# eurofima.net
KiCad netlist of a schematic drawn in EAGLE
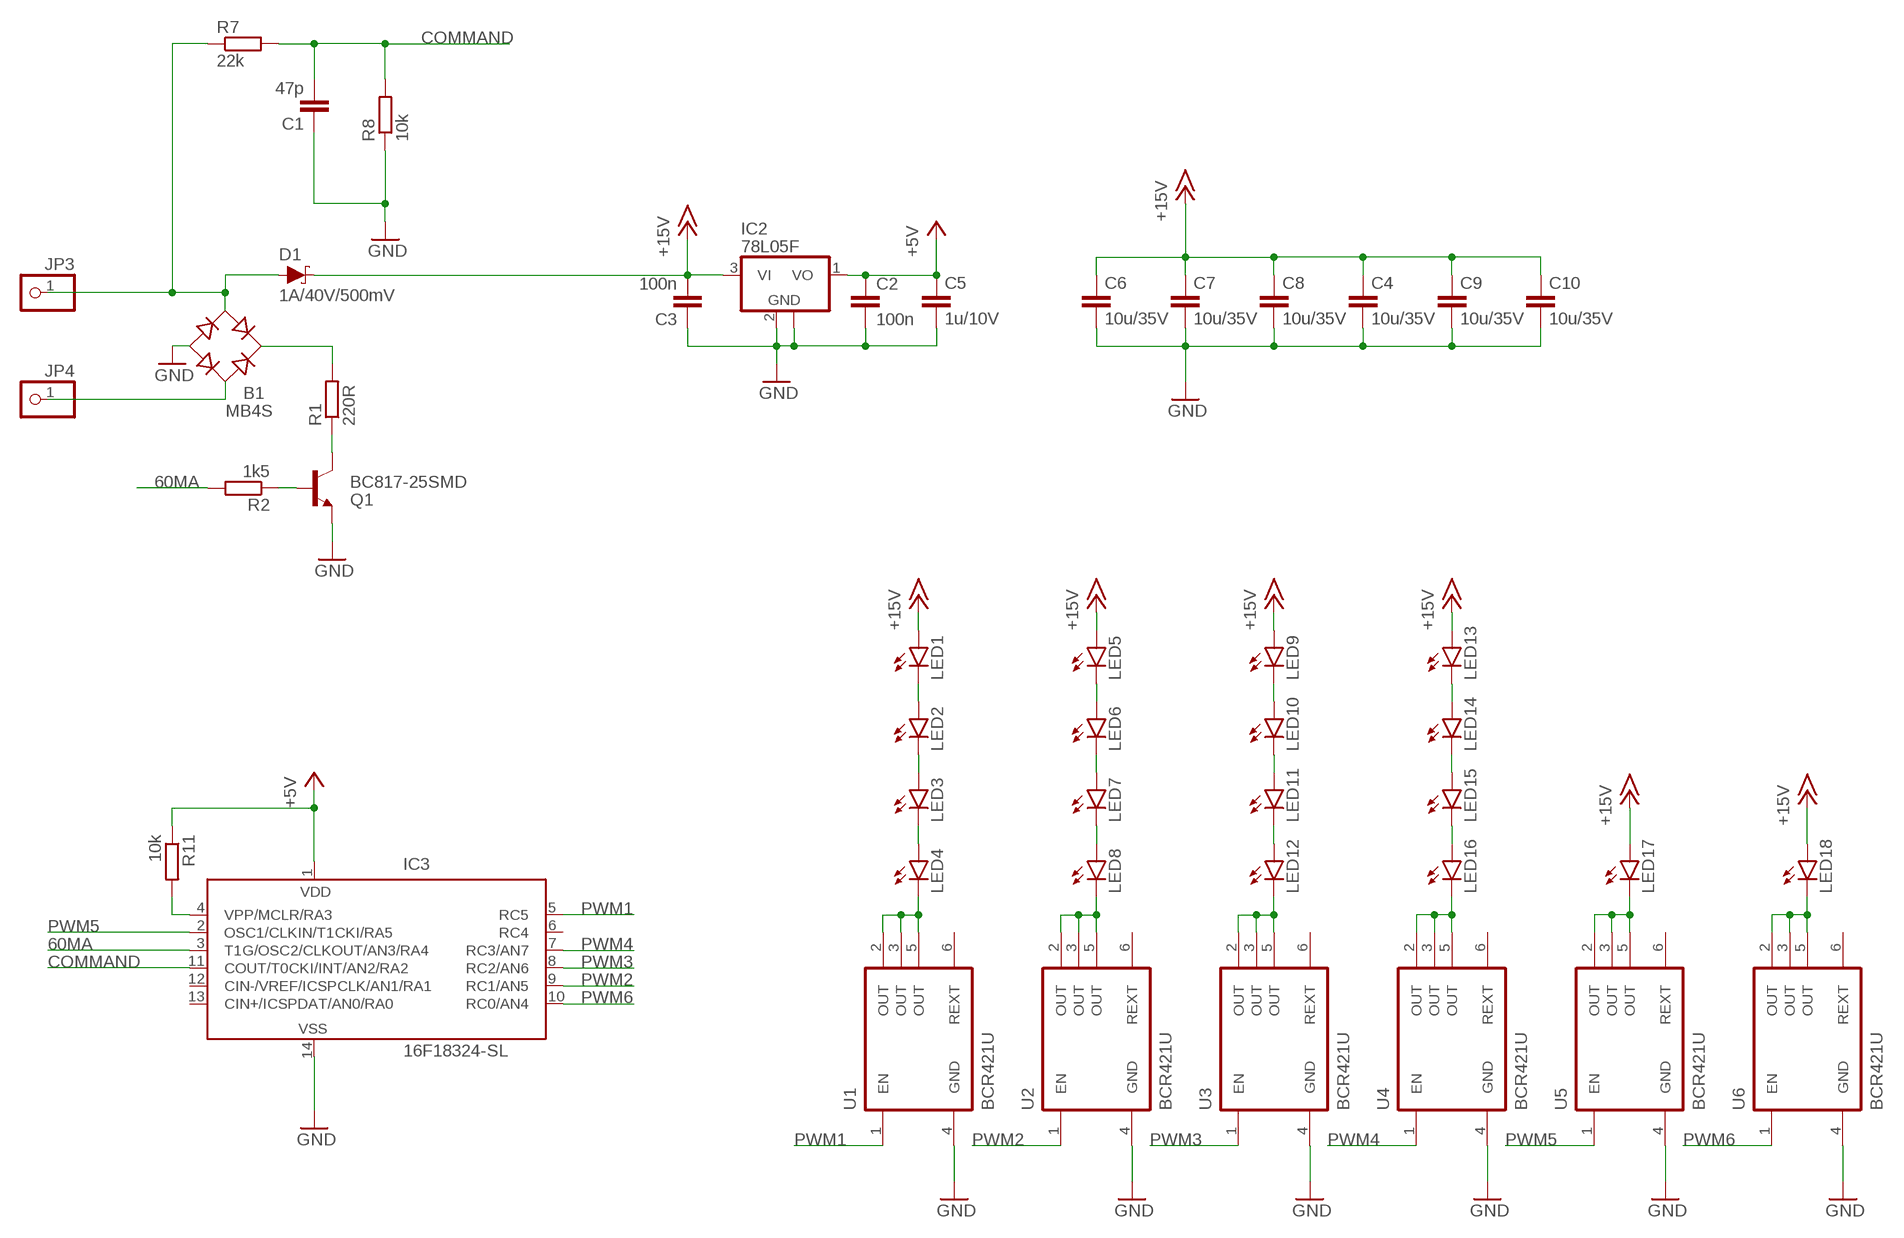
[diagram p0: schematic, sheet 1]

(export (version "E")
  (design (tool "Eeschema 10.0.6"))
  (components
    (comp (ref "B1")
      (value "MB4S")
      (footprint "eagle-import:SOIC-4")
      (libsource (lib "eagle-import") (part "MBS4"))
    )
    (comp (ref "C1")
      (value "47p")
      (footprint "eagle-import:C0805")
      (libsource (lib "eagle-import") (part "C-EUC0805"))
    )
    (comp (ref "C2")
      (value "100n")
      (footprint "eagle-import:C3216")
      (libsource (lib "eagle-import") (part "C-EUC3216"))
    )
    (comp (ref "C3")
      (value "100n")
      (footprint "eagle-import:C3216")
      (libsource (lib "eagle-import") (part "C-EUC3216"))
    )
    (comp (ref "C4")
      (value "10u/35V")
      (footprint "eagle-import:C3216")
      (libsource (lib "eagle-import") (part "C-EUC3216"))
    )
    (comp (ref "C5")
      (value "1u/10V")
      (footprint "eagle-import:C3216")
      (libsource (lib "eagle-import") (part "C-EUC3216"))
    )
    (comp (ref "C6")
      (value "10u/35V")
      (footprint "eagle-import:C3216")
      (libsource (lib "eagle-import") (part "C-EUC3216"))
    )
    (comp (ref "C7")
      (value "10u/35V")
      (footprint "eagle-import:C3216")
      (libsource (lib "eagle-import") (part "C-EUC3216"))
    )
    (comp (ref "C8")
      (value "10u/35V")
      (footprint "eagle-import:C3216")
      (libsource (lib "eagle-import") (part "C-EUC3216"))
    )
    (comp (ref "C9")
      (value "10u/35V")
      (footprint "eagle-import:C3216")
      (libsource (lib "eagle-import") (part "C-EUC3216"))
    )
    (comp (ref "C10")
      (value "10u/35V")
      (footprint "eagle-import:C3216")
      (libsource (lib "eagle-import") (part "C-EUC3216"))
    )
    (comp (ref "D1")
      (value "1A/40V/500mV")
      (footprint "eagle-import:SMA-DIODE")
      (libsource (lib "eagle-import") (part "DIODE-SCHOTTKY-SS14"))
    )
    (comp (ref "IC2")
      (value "78L05F")
      (footprint "eagle-import:SOT89")
      (libsource (lib "eagle-import") (part "78LF05"))
    )
    (comp (ref "IC3")
      (value "16F18324-SL")
      (footprint "eagle-import:SO-14")
      (fields (field (name "MF") "MICROCHIP") (field (name "MPN") "PIC16F676-I/SL"))
      (libsource (lib "eagle-import") (part "PIC16F676SL"))
    )
    (comp (ref "JP3")
      (value "PINHD-1X1")
      (footprint "eagle-import:1X01")
      (libsource (lib "eagle-import") (part "PINHD-1X1"))
    )
    (comp (ref "JP4")
      (value "PINHD-1X1")
      (footprint "eagle-import:1X01")
      (libsource (lib "eagle-import") (part "PINHD-1X1"))
    )
    (comp (ref "LED1")
      (value "LEDKA-3528ASYC")
      (footprint "eagle-import:KA-3528ASYC")
      (libsource (lib "eagle-import") (part "LEDKA-3528ASYC"))
    )
    (comp (ref "LED2")
      (value "LEDKA-3528ASYC")
      (footprint "eagle-import:KA-3528ASYC")
      (libsource (lib "eagle-import") (part "LEDKA-3528ASYC"))
    )
    (comp (ref "LED3")
      (value "LEDKA-3528ASYC")
      (footprint "eagle-import:KA-3528ASYC")
      (libsource (lib "eagle-import") (part "LEDKA-3528ASYC"))
    )
    (comp (ref "LED4")
      (value "LEDKA-3528ASYC")
      (footprint "eagle-import:KA-3528ASYC")
      (libsource (lib "eagle-import") (part "LEDKA-3528ASYC"))
    )
    (comp (ref "LED5")
      (value "LEDKA-3528ASYC")
      (footprint "eagle-import:KA-3528ASYC")
      (libsource (lib "eagle-import") (part "LEDKA-3528ASYC"))
    )
    (comp (ref "LED6")
      (value "LEDKA-3528ASYC")
      (footprint "eagle-import:KA-3528ASYC")
      (libsource (lib "eagle-import") (part "LEDKA-3528ASYC"))
    )
    (comp (ref "LED7")
      (value "LEDKA-3528ASYC")
      (footprint "eagle-import:KA-3528ASYC")
      (libsource (lib "eagle-import") (part "LEDKA-3528ASYC"))
    )
    (comp (ref "LED8")
      (value "LEDKA-3528ASYC")
      (footprint "eagle-import:KA-3528ASYC")
      (libsource (lib "eagle-import") (part "LEDKA-3528ASYC"))
    )
    (comp (ref "LED9")
      (value "LEDKA-3528ASYC")
      (footprint "eagle-import:KA-3528ASYC")
      (libsource (lib "eagle-import") (part "LEDKA-3528ASYC"))
    )
    (comp (ref "LED10")
      (value "LEDKA-3528ASYC")
      (footprint "eagle-import:KA-3528ASYC")
      (libsource (lib "eagle-import") (part "LEDKA-3528ASYC"))
    )
    (comp (ref "LED11")
      (value "LEDKA-3528ASYC")
      (footprint "eagle-import:KA-3528ASYC")
      (libsource (lib "eagle-import") (part "LEDKA-3528ASYC"))
    )
    (comp (ref "LED12")
      (value "LEDKA-3528ASYC")
      (footprint "eagle-import:KA-3528ASYC")
      (libsource (lib "eagle-import") (part "LEDKA-3528ASYC"))
    )
    (comp (ref "LED13")
      (value "LEDKA-3528ASYC")
      (footprint "eagle-import:KA-3528ASYC")
      (libsource (lib "eagle-import") (part "LEDKA-3528ASYC"))
    )
    (comp (ref "LED14")
      (value "LEDKA-3528ASYC")
      (footprint "eagle-import:KA-3528ASYC")
      (libsource (lib "eagle-import") (part "LEDKA-3528ASYC"))
    )
    (comp (ref "LED15")
      (value "LEDKA-3528ASYC")
      (footprint "eagle-import:KA-3528ASYC")
      (libsource (lib "eagle-import") (part "LEDKA-3528ASYC"))
    )
    (comp (ref "LED16")
      (value "LEDKA-3528ASYC")
      (footprint "eagle-import:KA-3528ASYC")
      (libsource (lib "eagle-import") (part "LEDKA-3528ASYC"))
    )
    (comp (ref "LED17")
      (value "LED3MM")
      (footprint "eagle-import:LED3MM")
      (libsource (lib "eagle-import") (part "LED3MM"))
    )
    (comp (ref "LED18")
      (value "LED3MM")
      (footprint "eagle-import:LED3MM")
      (libsource (lib "eagle-import") (part "LED3MM"))
    )
    (comp (ref "Q1")
      (value "BC817-25SMD")
      (footprint "eagle-import:SOT23-BEC")
      (libsource (lib "eagle-import") (part "BC817SMD-25"))
    )
    (comp (ref "R1")
      (value "220R")
      (footprint "eagle-import:R1206")
      (libsource (lib "eagle-import") (part "R-EU_R1206"))
    )
    (comp (ref "R2")
      (value "1k5")
      (footprint "eagle-import:R1206")
      (libsource (lib "eagle-import") (part "R-EU_R1206"))
    )
    (comp (ref "R7")
      (value "22k")
      (footprint "eagle-import:R1206")
      (libsource (lib "eagle-import") (part "R-EU_R1206"))
    )
    (comp (ref "R8")
      (value "10k")
      (footprint "eagle-import:R1206")
      (libsource (lib "eagle-import") (part "R-EU_R1206"))
    )
    (comp (ref "R11")
      (value "10k")
      (footprint "eagle-import:R1206")
      (libsource (lib "eagle-import") (part "R-EU_R1206"))
    )
    (comp (ref "U1")
      (value "BCR421U")
      (footprint "eagle-import:SC74-6")
      (fields (field (name "MF") "Infineon"))
      (libsource (lib "eagle-import") (part "BCR421U"))
    )
    (comp (ref "U2")
      (value "BCR421U")
      (footprint "eagle-import:SC74-6")
      (fields (field (name "MF") "Infineon"))
      (libsource (lib "eagle-import") (part "BCR421U"))
    )
    (comp (ref "U3")
      (value "BCR421U")
      (footprint "eagle-import:SC74-6")
      (fields (field (name "MF") "Infineon"))
      (libsource (lib "eagle-import") (part "BCR421U"))
    )
    (comp (ref "U4")
      (value "BCR421U")
      (footprint "eagle-import:SC74-6")
      (fields (field (name "MF") "Infineon"))
      (libsource (lib "eagle-import") (part "BCR421U"))
    )
    (comp (ref "U5")
      (value "BCR421U")
      (footprint "eagle-import:SC74-6")
      (fields (field (name "MF") "Infineon"))
      (libsource (lib "eagle-import") (part "BCR421U"))
    )
    (comp (ref "U6")
      (value "BCR421U")
      (footprint "eagle-import:SC74-6")
      (fields (field (name "MF") "Infineon"))
      (libsource (lib "eagle-import") (part "BCR421U"))
    )
  )
  (nets
    (net (code "1") (name "+5V") (class "Default")
      (node (ref "C2") (pin "1") (pinfunction "1_1") (pintype "passive"))
      (node (ref "C5") (pin "1") (pinfunction "1_1") (pintype "passive"))
      (node (ref "IC2") (pin "1") (pinfunction "VO_1") (pintype "passive"))
      (node (ref "IC3") (pin "1") (pinfunction "VDD_1") (pintype "power_in"))
      (node (ref "R11") (pin "1") (pinfunction "1_1") (pintype "passive"))
    )
    (net (code "2") (name "+15V") (class "Default")
      (node (ref "C10") (pin "1") (pinfunction "1_1") (pintype "passive"))
      (node (ref "C3") (pin "2") (pinfunction "2_2") (pintype "passive"))
      (node (ref "C4") (pin "1") (pinfunction "1_1") (pintype "passive"))
      (node (ref "C6") (pin "1") (pinfunction "1_1") (pintype "passive"))
      (node (ref "C7") (pin "1") (pinfunction "1_1") (pintype "passive"))
      (node (ref "C8") (pin "1") (pinfunction "1_1") (pintype "passive"))
      (node (ref "C9") (pin "1") (pinfunction "1_1") (pintype "passive"))
      (node (ref "D1") (pin "C") (pinfunction "C_C") (pintype "passive"))
      (node (ref "IC2") (pin "3") (pinfunction "VI_3") (pintype "input"))
      (node (ref "LED1") (pin "A") (pinfunction "A_A") (pintype "passive"))
      (node (ref "LED13") (pin "A") (pinfunction "A_A") (pintype "passive"))
      (node (ref "LED17") (pin "A") (pinfunction "A_A") (pintype "passive"))
      (node (ref "LED18") (pin "A") (pinfunction "A_A") (pintype "passive"))
      (node (ref "LED5") (pin "A") (pinfunction "A_A") (pintype "passive"))
      (node (ref "LED9") (pin "A") (pinfunction "A_A") (pintype "passive"))
    )
    (net (code "3") (name "/60MA") (class "Default")
      (node (ref "IC3") (pin "3") (pinfunction "T1G/OSC2/CLKOUT/AN3/RA4_3") (pintype "bidirectional"))
      (node (ref "R2") (pin "2") (pinfunction "2_2") (pintype "passive"))
    )
    (net (code "4") (name "/COMMAND") (class "Default")
      (node (ref "C1") (pin "2") (pinfunction "2_2") (pintype "passive"))
      (node (ref "IC3") (pin "11") (pinfunction "COUT/T0CKI/INT/AN2/RA2_11") (pintype "bidirectional"))
      (node (ref "R7") (pin "2") (pinfunction "2_2") (pintype "passive"))
      (node (ref "R8") (pin "2") (pinfunction "2_2") (pintype "passive"))
    )
    (net (code "5") (name "/PWM1") (class "Default")
      (node (ref "IC3") (pin "5") (pinfunction "RC5_5") (pintype "bidirectional"))
      (node (ref "U1") (pin "1") (pinfunction "EN_1") (pintype "input"))
    )
    (net (code "6") (name "/PWM2") (class "Default")
      (node (ref "IC3") (pin "9") (pinfunction "RC1/AN5_9") (pintype "bidirectional"))
      (node (ref "U2") (pin "1") (pinfunction "EN_1") (pintype "input"))
    )
    (net (code "7") (name "/PWM3") (class "Default")
      (node (ref "IC3") (pin "8") (pinfunction "RC2/AN6_8") (pintype "bidirectional"))
      (node (ref "U3") (pin "1") (pinfunction "EN_1") (pintype "input"))
    )
    (net (code "8") (name "/PWM4") (class "Default")
      (node (ref "IC3") (pin "7") (pinfunction "RC3/AN7_7") (pintype "bidirectional"))
      (node (ref "U4") (pin "1") (pinfunction "EN_1") (pintype "input"))
    )
    (net (code "9") (name "/PWM5") (class "Default")
      (node (ref "IC3") (pin "2") (pinfunction "OSC1/CLKIN/T1CKI/RA5_2") (pintype "bidirectional"))
      (node (ref "U5") (pin "1") (pinfunction "EN_1") (pintype "input"))
    )
    (net (code "10") (name "/PWM6") (class "Default")
      (node (ref "IC3") (pin "10") (pinfunction "RC0/AN4_10") (pintype "bidirectional"))
      (node (ref "U6") (pin "1") (pinfunction "EN_1") (pintype "input"))
    )
    (net (code "11") (name "GND") (class "Default")
      (node (ref "B1") (pin "-") (pinfunction "-_-") (pintype "passive"))
      (node (ref "C1") (pin "1") (pinfunction "1_1") (pintype "passive"))
      (node (ref "C10") (pin "2") (pinfunction "2_2") (pintype "passive"))
      (node (ref "C2") (pin "2") (pinfunction "2_2") (pintype "passive"))
      (node (ref "C3") (pin "1") (pinfunction "1_1") (pintype "passive"))
      (node (ref "C4") (pin "2") (pinfunction "2_2") (pintype "passive"))
      (node (ref "C5") (pin "2") (pinfunction "2_2") (pintype "passive"))
      (node (ref "C6") (pin "2") (pinfunction "2_2") (pintype "passive"))
      (node (ref "C7") (pin "2") (pinfunction "2_2") (pintype "passive"))
      (node (ref "C8") (pin "2") (pinfunction "2_2") (pintype "passive"))
      (node (ref "C9") (pin "2") (pinfunction "2_2") (pintype "passive"))
      (node (ref "IC2") (pin "2") (pinfunction "GND_2") (pintype "passive"))
      (node (ref "IC2") (pin "2@1") (pinfunction "GND_2@1") (pintype "passive"))
      (node (ref "IC3") (pin "14") (pinfunction "VSS_14") (pintype "power_in"))
      (node (ref "Q1") (pin "E") (pinfunction "E_E") (pintype "passive"))
      (node (ref "R8") (pin "1") (pinfunction "1_1") (pintype "passive"))
      (node (ref "U1") (pin "4") (pinfunction "GND_4") (pintype "input"))
      (node (ref "U2") (pin "4") (pinfunction "GND_4") (pintype "input"))
      (node (ref "U3") (pin "4") (pinfunction "GND_4") (pintype "input"))
      (node (ref "U4") (pin "4") (pinfunction "GND_4") (pintype "input"))
      (node (ref "U5") (pin "4") (pinfunction "GND_4") (pintype "input"))
      (node (ref "U6") (pin "4") (pinfunction "GND_4") (pintype "input"))
    )
    (net (code "12") (name "Net-(B1-AC1)") (class "Default")
      (node (ref "B1") (pin "~1") (pinfunction "AC1_~1") (pintype "passive"))
      (node (ref "D1") (pin "A") (pinfunction "A_A") (pintype "passive"))
      (node (ref "JP3") (pin "1") (pinfunction "1_1") (pintype "passive"))
      (node (ref "R7") (pin "1") (pinfunction "1_1") (pintype "passive"))
    )
    (net (code "13") (name "Net-(B1-AC2)") (class "Default")
      (node (ref "B1") (pin "~2") (pinfunction "AC2_~2") (pintype "passive"))
      (node (ref "JP4") (pin "1") (pinfunction "1_1") (pintype "passive"))
    )
    (net (code "14") (name "Net-(B1-Pad+)") (class "Default")
      (node (ref "B1") (pin "+") (pinfunction "+_+") (pintype "passive"))
      (node (ref "R1") (pin "2") (pinfunction "2_2") (pintype "passive"))
    )
    (net (code "15") (name "Net-(IC3-VPP{slash}MCLR{slash}RA3)") (class "Default")
      (node (ref "IC3") (pin "4") (pinfunction "VPP/MCLR/RA3_4") (pintype "input"))
      (node (ref "R11") (pin "2") (pinfunction "2_2") (pintype "passive"))
    )
    (net (code "16") (name "Net-(LED1-PadC)") (class "Default")
      (node (ref "LED1") (pin "C") (pinfunction "C_C") (pintype "passive"))
      (node (ref "LED2") (pin "A") (pinfunction "A_A") (pintype "passive"))
    )
    (net (code "17") (name "Net-(LED2-PadC)") (class "Default")
      (node (ref "LED2") (pin "C") (pinfunction "C_C") (pintype "passive"))
      (node (ref "LED3") (pin "A") (pinfunction "A_A") (pintype "passive"))
    )
    (net (code "18") (name "Net-(LED3-PadC)") (class "Default")
      (node (ref "LED3") (pin "C") (pinfunction "C_C") (pintype "passive"))
      (node (ref "LED4") (pin "A") (pinfunction "A_A") (pintype "passive"))
    )
    (net (code "19") (name "Net-(LED4-PadC)") (class "Default")
      (node (ref "LED4") (pin "C") (pinfunction "C_C") (pintype "passive"))
      (node (ref "U1") (pin "2") (pinfunction "OUT_2") (pintype "open_collector"))
      (node (ref "U1") (pin "3") (pinfunction "OUT_3") (pintype "open_collector"))
      (node (ref "U1") (pin "5") (pinfunction "OUT_5") (pintype "open_collector"))
    )
    (net (code "20") (name "Net-(LED5-PadC)") (class "Default")
      (node (ref "LED5") (pin "C") (pinfunction "C_C") (pintype "passive"))
      (node (ref "LED6") (pin "A") (pinfunction "A_A") (pintype "passive"))
    )
    (net (code "21") (name "Net-(LED6-PadC)") (class "Default")
      (node (ref "LED6") (pin "C") (pinfunction "C_C") (pintype "passive"))
      (node (ref "LED7") (pin "A") (pinfunction "A_A") (pintype "passive"))
    )
    (net (code "22") (name "Net-(LED7-PadC)") (class "Default")
      (node (ref "LED7") (pin "C") (pinfunction "C_C") (pintype "passive"))
      (node (ref "LED8") (pin "A") (pinfunction "A_A") (pintype "passive"))
    )
    (net (code "23") (name "Net-(LED8-PadC)") (class "Default")
      (node (ref "LED8") (pin "C") (pinfunction "C_C") (pintype "passive"))
      (node (ref "U2") (pin "2") (pinfunction "OUT_2") (pintype "open_collector"))
      (node (ref "U2") (pin "3") (pinfunction "OUT_3") (pintype "open_collector"))
      (node (ref "U2") (pin "5") (pinfunction "OUT_5") (pintype "open_collector"))
    )
    (net (code "24") (name "Net-(LED10-PadA)") (class "Default")
      (node (ref "LED10") (pin "A") (pinfunction "A_A") (pintype "passive"))
      (node (ref "LED9") (pin "C") (pinfunction "C_C") (pintype "passive"))
    )
    (net (code "25") (name "Net-(LED10-PadC)") (class "Default")
      (node (ref "LED10") (pin "C") (pinfunction "C_C") (pintype "passive"))
      (node (ref "LED11") (pin "A") (pinfunction "A_A") (pintype "passive"))
    )
    (net (code "26") (name "Net-(LED11-PadC)") (class "Default")
      (node (ref "LED11") (pin "C") (pinfunction "C_C") (pintype "passive"))
      (node (ref "LED12") (pin "A") (pinfunction "A_A") (pintype "passive"))
    )
    (net (code "27") (name "Net-(LED12-PadC)") (class "Default")
      (node (ref "LED12") (pin "C") (pinfunction "C_C") (pintype "passive"))
      (node (ref "U3") (pin "2") (pinfunction "OUT_2") (pintype "open_collector"))
      (node (ref "U3") (pin "3") (pinfunction "OUT_3") (pintype "open_collector"))
      (node (ref "U3") (pin "5") (pinfunction "OUT_5") (pintype "open_collector"))
    )
    (net (code "28") (name "Net-(LED13-PadC)") (class "Default")
      (node (ref "LED13") (pin "C") (pinfunction "C_C") (pintype "passive"))
      (node (ref "LED14") (pin "A") (pinfunction "A_A") (pintype "passive"))
    )
    (net (code "29") (name "Net-(LED14-PadC)") (class "Default")
      (node (ref "LED14") (pin "C") (pinfunction "C_C") (pintype "passive"))
      (node (ref "LED15") (pin "A") (pinfunction "A_A") (pintype "passive"))
    )
    (net (code "30") (name "Net-(LED15-PadC)") (class "Default")
      (node (ref "LED15") (pin "C") (pinfunction "C_C") (pintype "passive"))
      (node (ref "LED16") (pin "A") (pinfunction "A_A") (pintype "passive"))
    )
    (net (code "31") (name "Net-(LED16-PadC)") (class "Default")
      (node (ref "LED16") (pin "C") (pinfunction "C_C") (pintype "passive"))
      (node (ref "U4") (pin "2") (pinfunction "OUT_2") (pintype "open_collector"))
      (node (ref "U4") (pin "3") (pinfunction "OUT_3") (pintype "open_collector"))
      (node (ref "U4") (pin "5") (pinfunction "OUT_5") (pintype "open_collector"))
    )
    (net (code "32") (name "Net-(LED17-C)") (class "Default")
      (node (ref "LED17") (pin "K") (pinfunction "C_K") (pintype "passive"))
      (node (ref "U5") (pin "2") (pinfunction "OUT_2") (pintype "open_collector"))
      (node (ref "U5") (pin "3") (pinfunction "OUT_3") (pintype "open_collector"))
      (node (ref "U5") (pin "5") (pinfunction "OUT_5") (pintype "open_collector"))
    )
    (net (code "33") (name "Net-(LED18-C)") (class "Default")
      (node (ref "LED18") (pin "K") (pinfunction "C_K") (pintype "passive"))
      (node (ref "U6") (pin "2") (pinfunction "OUT_2") (pintype "open_collector"))
      (node (ref "U6") (pin "3") (pinfunction "OUT_3") (pintype "open_collector"))
      (node (ref "U6") (pin "5") (pinfunction "OUT_5") (pintype "open_collector"))
    )
    (net (code "34") (name "Net-(Q1-PadB)") (class "Default")
      (node (ref "Q1") (pin "B") (pinfunction "B_B") (pintype "passive"))
      (node (ref "R2") (pin "1") (pinfunction "1_1") (pintype "passive"))
    )
    (net (code "35") (name "Net-(Q1-PadC)") (class "Default")
      (node (ref "Q1") (pin "C") (pinfunction "C_C") (pintype "passive"))
      (node (ref "R1") (pin "1") (pinfunction "1_1") (pintype "passive"))
    )
    (net (code "36") (name "unconnected-(IC3-CIN+{slash}ICSPDAT{slash}AN0{slash}RA0-Pad13)") (class "Default")
      (node (ref "IC3") (pin "13") (pinfunction "CIN+/ICSPDAT/AN0/RA0_13") (pintype "bidirectional"))
    )
    (net (code "37") (name "unconnected-(IC3-CIN-{slash}VREF{slash}ICSPCLK{slash}AN1{slash}RA1-Pad12)") (class "Default")
      (node (ref "IC3") (pin "12") (pinfunction "CIN-/VREF/ICSPCLK/AN1/RA1_12") (pintype "bidirectional"))
    )
    (net (code "38") (name "unconnected-(IC3-RC4-Pad6)") (class "Default")
      (node (ref "IC3") (pin "6") (pinfunction "RC4_6") (pintype "bidirectional"))
    )
    (net (code "39") (name "unconnected-(U1-REXT-Pad6)") (class "Default")
      (node (ref "U1") (pin "6") (pinfunction "REXT_6") (pintype "bidirectional"))
    )
    (net (code "40") (name "unconnected-(U2-REXT-Pad6)") (class "Default")
      (node (ref "U2") (pin "6") (pinfunction "REXT_6") (pintype "bidirectional"))
    )
    (net (code "41") (name "unconnected-(U3-REXT-Pad6)") (class "Default")
      (node (ref "U3") (pin "6") (pinfunction "REXT_6") (pintype "bidirectional"))
    )
    (net (code "42") (name "unconnected-(U4-REXT-Pad6)") (class "Default")
      (node (ref "U4") (pin "6") (pinfunction "REXT_6") (pintype "bidirectional"))
    )
    (net (code "43") (name "unconnected-(U5-REXT-Pad6)") (class "Default")
      (node (ref "U5") (pin "6") (pinfunction "REXT_6") (pintype "bidirectional"))
    )
    (net (code "44") (name "unconnected-(U6-REXT-Pad6)") (class "Default")
      (node (ref "U6") (pin "6") (pinfunction "REXT_6") (pintype "bidirectional"))
    )
  )
)
